# ProPrj_Framethrower_Denise_Rev1.net
KiCad netlist of a schematic drawn in EasyEDA Pro
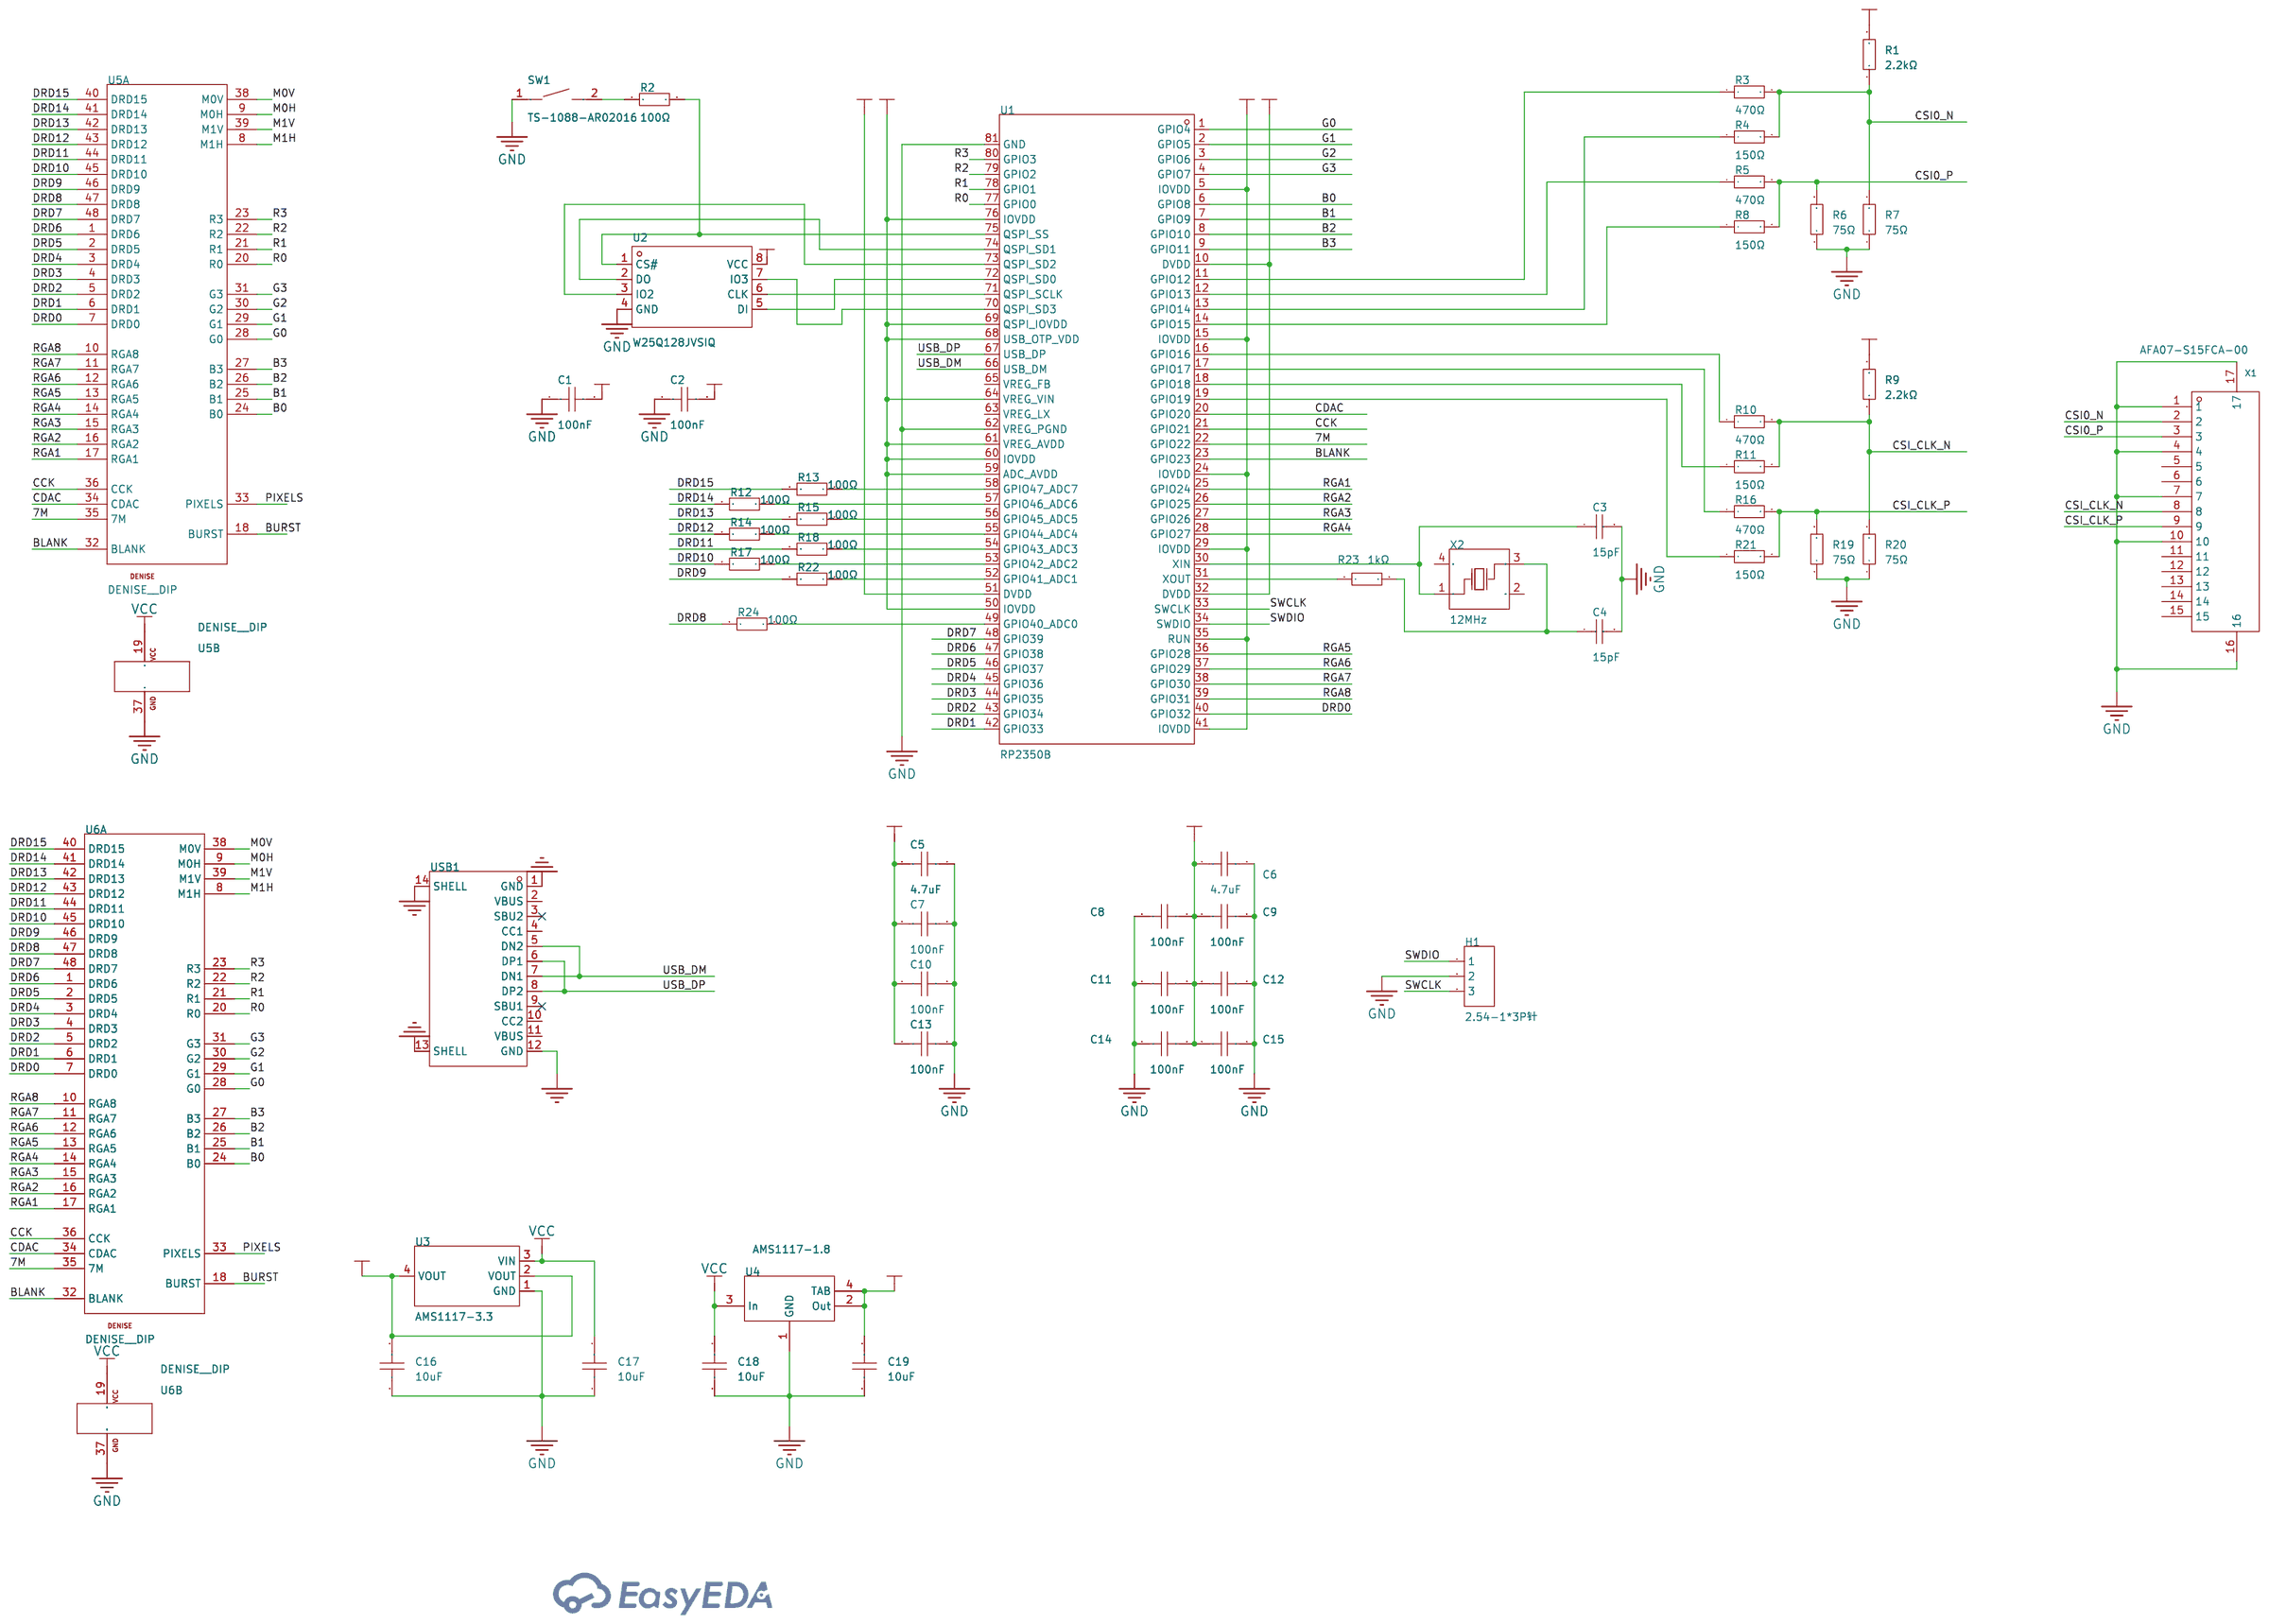
[diagram p0: schematic sheet]

(export (version "E")
  (design (tool "Eeschema 10.0.6"))
  (components
    (comp (ref "C1")
      (value "100nF")
      (footprint "easyedapro:C0603")
      (description "Capacitance:100nF Tolerance:±10% Tolerance:±10% Voltage Rating:50V Temperature Coefficient:X7R")
      (fields
        (field (name "Manufacturer Part") "CC0603KRX7R9BB104")
        (field (name "Manufacturer") "YAGEO(国巨)")
      )
      (libsource (lib "easyedapro") (part "CC0603KRX7R9BB104"))
    )
    (comp (ref "C2")
      (value "100nF")
      (footprint "easyedapro:C0603")
      (description "Capacitance:100nF Tolerance:±10% Tolerance:±10% Voltage Rating:50V Temperature Coefficient:X7R")
      (fields
        (field (name "Manufacturer Part") "CC0603KRX7R9BB104")
        (field (name "Manufacturer") "YAGEO(国巨)")
      )
      (libsource (lib "easyedapro") (part "CC0603KRX7R9BB104"))
    )
    (comp (ref "C3")
      (value "15pF")
      (footprint "easyedapro:C0603")
      (fields
        (field (name "Manufacturer Part") "CL10C150JB8NNNC")
        (field (name "Manufacturer") "SAMSUNG(三星)")
      )
      (libsource (lib "easyedapro") (part "CL10C150JB8NNNC"))
    )
    (comp (ref "C4")
      (value "15pF")
      (footprint "easyedapro:C0603")
      (fields
        (field (name "Manufacturer Part") "CL10C150JB8NNNC")
        (field (name "Manufacturer") "SAMSUNG(三星)")
      )
      (libsource (lib "easyedapro") (part "CL10C150JB8NNNC"))
    )
    (comp (ref "C5")
      (value "4.7uF")
      (footprint "easyedapro:C0603")
      (fields
        (field (name "Manufacturer Part") "CL10A475KO8NNNC")
        (field (name "Manufacturer") "SAMSUNG(三星)")
      )
      (libsource (lib "easyedapro") (part "CL10A475KO8NNNC"))
    )
    (comp (ref "C6")
      (value "4.7uF")
      (footprint "easyedapro:C0603")
      (fields
        (field (name "Manufacturer Part") "CL10A475KO8NNNC")
        (field (name "Manufacturer") "SAMSUNG(三星)")
      )
      (libsource (lib "easyedapro") (part "CL10A475KO8NNNC"))
    )
    (comp (ref "C7")
      (value "100nF")
      (footprint "easyedapro:C0603")
      (description "Capacitance:100nF Tolerance:±10% Tolerance:±10% Voltage Rating:50V Temperature Coefficient:X7R")
      (fields
        (field (name "Manufacturer Part") "CC0603KRX7R9BB104")
        (field (name "Manufacturer") "YAGEO(国巨)")
      )
      (libsource (lib "easyedapro") (part "CC0603KRX7R9BB104"))
    )
    (comp (ref "C8")
      (value "100nF")
      (footprint "easyedapro:C0603")
      (description "Capacitance:100nF Tolerance:±10% Tolerance:±10% Voltage Rating:50V Temperature Coefficient:X7R")
      (fields
        (field (name "Manufacturer Part") "CC0603KRX7R9BB104")
        (field (name "Manufacturer") "YAGEO(国巨)")
      )
      (libsource (lib "easyedapro") (part "CC0603KRX7R9BB104"))
    )
    (comp (ref "C9")
      (value "100nF")
      (footprint "easyedapro:C0603")
      (description "Capacitance:100nF Tolerance:±10% Tolerance:±10% Voltage Rating:50V Temperature Coefficient:X7R")
      (fields
        (field (name "Manufacturer Part") "CC0603KRX7R9BB104")
        (field (name "Manufacturer") "YAGEO(国巨)")
      )
      (libsource (lib "easyedapro") (part "CC0603KRX7R9BB104"))
    )
    (comp (ref "C10")
      (value "100nF")
      (footprint "easyedapro:C0603")
      (description "Capacitance:100nF Tolerance:±10% Tolerance:±10% Voltage Rating:50V Temperature Coefficient:X7R")
      (fields
        (field (name "Manufacturer Part") "CC0603KRX7R9BB104")
        (field (name "Manufacturer") "YAGEO(国巨)")
      )
      (libsource (lib "easyedapro") (part "CC0603KRX7R9BB104"))
    )
    (comp (ref "C11")
      (value "100nF")
      (footprint "easyedapro:C0603")
      (description "Capacitance:100nF Tolerance:±10% Tolerance:±10% Voltage Rating:50V Temperature Coefficient:X7R")
      (fields
        (field (name "Manufacturer Part") "CC0603KRX7R9BB104")
        (field (name "Manufacturer") "YAGEO(国巨)")
      )
      (libsource (lib "easyedapro") (part "CC0603KRX7R9BB104"))
    )
    (comp (ref "C12")
      (value "100nF")
      (footprint "easyedapro:C0603")
      (description "Capacitance:100nF Tolerance:±10% Tolerance:±10% Voltage Rating:50V Temperature Coefficient:X7R")
      (fields
        (field (name "Manufacturer Part") "CC0603KRX7R9BB104")
        (field (name "Manufacturer") "YAGEO(国巨)")
      )
      (libsource (lib "easyedapro") (part "CC0603KRX7R9BB104"))
    )
    (comp (ref "C13")
      (value "100nF")
      (footprint "easyedapro:C0603")
      (description "Capacitance:100nF Tolerance:±10% Tolerance:±10% Voltage Rating:50V Temperature Coefficient:X7R")
      (fields
        (field (name "Manufacturer Part") "CC0603KRX7R9BB104")
        (field (name "Manufacturer") "YAGEO(国巨)")
      )
      (libsource (lib "easyedapro") (part "CC0603KRX7R9BB104"))
    )
    (comp (ref "C14")
      (value "100nF")
      (footprint "easyedapro:C0603")
      (description "Capacitance:100nF Tolerance:±10% Tolerance:±10% Voltage Rating:50V Temperature Coefficient:X7R")
      (fields
        (field (name "Manufacturer Part") "CC0603KRX7R9BB104")
        (field (name "Manufacturer") "YAGEO(国巨)")
      )
      (libsource (lib "easyedapro") (part "CC0603KRX7R9BB104"))
    )
    (comp (ref "C15")
      (value "100nF")
      (footprint "easyedapro:C0603")
      (description "Capacitance:100nF Tolerance:±10% Tolerance:±10% Voltage Rating:50V Temperature Coefficient:X7R")
      (fields
        (field (name "Manufacturer Part") "CC0603KRX7R9BB104")
        (field (name "Manufacturer") "YAGEO(国巨)")
      )
      (libsource (lib "easyedapro") (part "CC0603KRX7R9BB104"))
    )
    (comp (ref "C16")
      (value "10uF")
      (footprint "easyedapro:C0603")
      (fields
        (field (name "Manufacturer Part") "CL10A106KP8NNNC")
        (field (name "Manufacturer") "SAMSUNG(三星)")
      )
      (libsource (lib "easyedapro") (part "CL10A106KP8NNNC"))
    )
    (comp (ref "C17")
      (value "10uF")
      (footprint "easyedapro:C0603")
      (fields
        (field (name "Manufacturer Part") "CL10A106KP8NNNC")
        (field (name "Manufacturer") "SAMSUNG(三星)")
      )
      (libsource (lib "easyedapro") (part "CL10A106KP8NNNC"))
    )
    (comp (ref "C18")
      (value "10uF")
      (footprint "easyedapro:C0603")
      (fields
        (field (name "Manufacturer Part") "CL10A106KP8NNNC")
        (field (name "Manufacturer") "SAMSUNG(三星)")
      )
      (libsource (lib "easyedapro") (part "CL10A106KP8NNNC"))
    )
    (comp (ref "C19")
      (value "10uF")
      (footprint "easyedapro:C0603")
      (fields
        (field (name "Manufacturer Part") "CL10A106KP8NNNC")
        (field (name "Manufacturer") "SAMSUNG(三星)")
      )
      (libsource (lib "easyedapro") (part "CL10A106KP8NNNC"))
    )
    (comp (ref "H1")
      (value "2.54-1*3P针")
      (footprint "easyedapro:HDR-TH_3P-P2.54-V-M-1")
      (fields (field (name "Manufacturer") "BOOMELE(博穆精密)"))
      (libsource (lib "easyedapro") (part "Header-Male-2.54_1x3"))
    )
    (comp (ref "R1")
      (value "2.2kΩ")
      (footprint "easyedapro:R0603")
      (fields
        (field (name "Manufacturer Part") "0603WAF2201T5E")
        (field (name "Manufacturer") "UNI-ROYAL(厚声)")
      )
      (libsource (lib "easyedapro") (part "0603WAF5600T5E"))
    )
    (comp (ref "R2")
      (value "100Ω")
      (footprint "easyedapro:R0603")
      (fields
        (field (name "Manufacturer Part") "0603WAF1000T5E")
        (field (name "Manufacturer") "UNI-ROYAL(厚声)")
      )
      (libsource (lib "easyedapro") (part "0603WAF1000T5E"))
    )
    (comp (ref "R3")
      (value "470Ω")
      (footprint "easyedapro:R0603")
      (fields
        (field (name "Manufacturer Part") "0603WAF4700T5E")
        (field (name "Manufacturer") "UNI-ROYAL(厚声)")
      )
      (libsource (lib "easyedapro") (part "0603WAF2400T5E"))
    )
    (comp (ref "R4")
      (value "150Ω")
      (footprint "easyedapro:R0603")
      (fields
        (field (name "Manufacturer Part") "0603WAF1500T5E")
        (field (name "Manufacturer") "UNI-ROYAL(厚声)")
      )
      (libsource (lib "easyedapro") (part "0603WAF750JT5E"))
    )
    (comp (ref "R5")
      (value "470Ω")
      (footprint "easyedapro:R0603")
      (fields
        (field (name "Manufacturer Part") "0603WAF4700T5E")
        (field (name "Manufacturer") "UNI-ROYAL(厚声)")
      )
      (libsource (lib "easyedapro") (part "0603WAF2400T5E"))
    )
    (comp (ref "R6")
      (value "75Ω")
      (footprint "easyedapro:R0603")
      (fields
        (field (name "Manufacturer Part") "0603WAF750JT5E")
        (field (name "Manufacturer") "UNI-ROYAL(厚声)")
      )
      (libsource (lib "easyedapro") (part "0603WAF270JT5E"))
    )
    (comp (ref "R7")
      (value "75Ω")
      (footprint "easyedapro:R0603")
      (fields
        (field (name "Manufacturer Part") "0603WAF750JT5E")
        (field (name "Manufacturer") "UNI-ROYAL(厚声)")
      )
      (libsource (lib "easyedapro") (part "0603WAF270JT5E"))
    )
    (comp (ref "R8")
      (value "150Ω")
      (footprint "easyedapro:R0603")
      (fields
        (field (name "Manufacturer Part") "0603WAF1500T5E")
        (field (name "Manufacturer") "UNI-ROYAL(厚声)")
      )
      (libsource (lib "easyedapro") (part "0603WAF750JT5E"))
    )
    (comp (ref "R9")
      (value "2.2kΩ")
      (footprint "easyedapro:R0603")
      (fields
        (field (name "Manufacturer Part") "0603WAF2201T5E")
        (field (name "Manufacturer") "UNI-ROYAL(厚声)")
      )
      (libsource (lib "easyedapro") (part "0603WAF5600T5E"))
    )
    (comp (ref "R10")
      (value "470Ω")
      (footprint "easyedapro:R0603")
      (fields
        (field (name "Manufacturer Part") "0603WAF4700T5E")
        (field (name "Manufacturer") "UNI-ROYAL(厚声)")
      )
      (libsource (lib "easyedapro") (part "0603WAF2400T5E"))
    )
    (comp (ref "R11")
      (value "150Ω")
      (footprint "easyedapro:R0603")
      (fields
        (field (name "Manufacturer Part") "0603WAF1500T5E")
        (field (name "Manufacturer") "UNI-ROYAL(厚声)")
      )
      (libsource (lib "easyedapro") (part "0603WAF750JT5E"))
    )
    (comp (ref "R12")
      (value "100Ω")
      (footprint "easyedapro:R0603")
      (fields
        (field (name "Manufacturer Part") "0603WAF1000T5E")
        (field (name "Manufacturer") "UNI-ROYAL(厚声)")
      )
      (libsource (lib "easyedapro") (part "0603WAF1000T5E"))
    )
    (comp (ref "R13")
      (value "100Ω")
      (footprint "easyedapro:R0603")
      (fields
        (field (name "Manufacturer Part") "0603WAF1000T5E")
        (field (name "Manufacturer") "UNI-ROYAL(厚声)")
      )
      (libsource (lib "easyedapro") (part "0603WAF1000T5E"))
    )
    (comp (ref "R14")
      (value "100Ω")
      (footprint "easyedapro:R0603")
      (fields
        (field (name "Manufacturer Part") "0603WAF1000T5E")
        (field (name "Manufacturer") "UNI-ROYAL(厚声)")
      )
      (libsource (lib "easyedapro") (part "0603WAF1000T5E"))
    )
    (comp (ref "R15")
      (value "100Ω")
      (footprint "easyedapro:R0603")
      (fields
        (field (name "Manufacturer Part") "0603WAF1000T5E")
        (field (name "Manufacturer") "UNI-ROYAL(厚声)")
      )
      (libsource (lib "easyedapro") (part "0603WAF1000T5E"))
    )
    (comp (ref "R16")
      (value "470Ω")
      (footprint "easyedapro:R0603")
      (fields
        (field (name "Manufacturer Part") "0603WAF4700T5E")
        (field (name "Manufacturer") "UNI-ROYAL(厚声)")
      )
      (libsource (lib "easyedapro") (part "0603WAF2400T5E"))
    )
    (comp (ref "R17")
      (value "100Ω")
      (footprint "easyedapro:R0603")
      (fields
        (field (name "Manufacturer Part") "0603WAF1000T5E")
        (field (name "Manufacturer") "UNI-ROYAL(厚声)")
      )
      (libsource (lib "easyedapro") (part "0603WAF1000T5E"))
    )
    (comp (ref "R18")
      (value "100Ω")
      (footprint "easyedapro:R0603")
      (fields
        (field (name "Manufacturer Part") "0603WAF1000T5E")
        (field (name "Manufacturer") "UNI-ROYAL(厚声)")
      )
      (libsource (lib "easyedapro") (part "0603WAF1000T5E"))
    )
    (comp (ref "R19")
      (value "75Ω")
      (footprint "easyedapro:R0603")
      (fields
        (field (name "Manufacturer Part") "0603WAF750JT5E")
        (field (name "Manufacturer") "UNI-ROYAL(厚声)")
      )
      (libsource (lib "easyedapro") (part "0603WAF270JT5E"))
    )
    (comp (ref "R20")
      (value "75Ω")
      (footprint "easyedapro:R0603")
      (fields
        (field (name "Manufacturer Part") "0603WAF750JT5E")
        (field (name "Manufacturer") "UNI-ROYAL(厚声)")
      )
      (libsource (lib "easyedapro") (part "0603WAF270JT5E"))
    )
    (comp (ref "R21")
      (value "150Ω")
      (footprint "easyedapro:R0603")
      (fields
        (field (name "Manufacturer Part") "0603WAF1500T5E")
        (field (name "Manufacturer") "UNI-ROYAL(厚声)")
      )
      (libsource (lib "easyedapro") (part "0603WAF750JT5E"))
    )
    (comp (ref "R22")
      (value "100Ω")
      (footprint "easyedapro:R0603")
      (fields
        (field (name "Manufacturer Part") "0603WAF1000T5E")
        (field (name "Manufacturer") "UNI-ROYAL(厚声)")
      )
      (libsource (lib "easyedapro") (part "0603WAF1000T5E"))
    )
    (comp (ref "R23")
      (value "1kΩ")
      (footprint "easyedapro:R0603")
      (fields
        (field (name "Manufacturer Part") "0603WAF1001T5E")
        (field (name "Manufacturer") "UNI-ROYAL(厚声)")
      )
      (libsource (lib "easyedapro") (part "0603WAF1001T5E"))
    )
    (comp (ref "R24")
      (value "100Ω")
      (footprint "easyedapro:R0603")
      (fields
        (field (name "Manufacturer Part") "0603WAF1000T5E")
        (field (name "Manufacturer") "UNI-ROYAL(厚声)")
      )
      (libsource (lib "easyedapro") (part "0603WAF1000T5E"))
    )
    (comp (ref "SW1")
      (value "TS-1088-AR02016")
      (footprint "easyedapro:SW-SMD_L3.9-W3.0-P4.45")
      (fields (field (name "Manufacturer") "XUNPU(讯普)"))
      (libsource (lib "easyedapro") (part "TS-1088-AR02016"))
    )
    (comp (ref "U1")
      (value "RP2350B")
      (footprint "easyedapro:QFN-80_L10.0-W10.0-P0.40-TL-EP3.4")
      (fields (field (name "Manufacturer") "Raspberry Pi(树莓派)"))
      (libsource (lib "easyedapro") (part "RP2350B_C42415655"))
    )
    (comp (ref "U2")
      (value "W25Q128JVSIQ")
      (footprint "easyedapro:SOIC-8_L5.3-W5.3-P1.27-LS8.0-BL")
      (fields (field (name "Manufacturer") "WINBOND(华邦)"))
      (libsource (lib "easyedapro") (part "W25Q128JVSIQTR"))
    )
    (comp (ref "U3")
      (value "AMS1117-3.3")
      (footprint "easyedapro:SOT-223-3_L6.5-W3.4-P2.30-LS7.0-BR")
      (fields (field (name "Manufacturer") "AMS"))
      (libsource (lib "easyedapro") (part "AMS1117-3.3"))
    )
    (comp (ref "U4")
      (value "AMS1117-1.8")
      (footprint "easyedapro:SOT-223-4_L6.5-W3.5-P2.30-LS7.0-BR")
      (fields (field (name "Manufacturer") "AMS"))
      (libsource (lib "easyedapro") (part "AMS1117-1.8"))
    )
    (comp (ref "U5")
      (value "DENISE__DIP")
      (footprint "easyedapro:DIP48-6")
      (libsource (lib "easyedapro") (part "DENISE__DIP"))
    )
    (comp (ref "U6")
      (value "DENISE__DIP")
      (footprint "easyedapro:DIP48-6")
      (libsource (lib "easyedapro") (part "DENISE__DIP"))
    )
    (comp (ref "USB1")
      (value "TYPE-C 16PIN 2MD(073)")
      (footprint "easyedapro:USB-C-SMD_TYPE-C-6PIN-2MD-073")
      (description "连接器类型:Type-C;标准:-;公母:母;端口数量:1;触点数量:16P;安装方式:卧贴;额定电流 - 电源:5A;工作温度范围:-25°C~+85°C;")
      (fields (field (name "Manufacturer") "SHOU HAN(首韩)"))
      (libsource (lib "easyedapro") (part "TYPE-C 16PIN 2MD(073)"))
    )
    (comp (ref "X1")
      (value "AFA07-S15FCA-00")
      (footprint "easyedapro:FPC-SMD_15P-P1.00_JS_AFA07-S15XXX")
      (fields (field (name "Manufacturer") "JS(钜硕电子)"))
      (libsource (lib "easyedapro") (part "AFA07-S15FCA-00"))
    )
    (comp (ref "X2")
      (value "12MHz")
      (footprint "easyedapro:CRYSTAL-SMD_4P-L3.2-W2.5-BL")
      (fields (field (name "Manufacturer Part") "X322512MSB4SI") (field (name "Manufacturer") "YXC(扬兴晶振)"))
      (libsource (lib "easyedapro") (part "X322512MSB4SI"))
    )
  )
  (nets
    (net (code "1") (name "/7M") (class "Default")
      (node (ref "U1") (pin "22") (pinfunction "GPIO22_22") (pintype "unspecified"))
      (node (ref "U5") (pin "35") (pinfunction "7M_35") (pintype "input"))
      (node (ref "U6") (pin "35") (pinfunction "7M_35") (pintype "input"))
    )
    (net (code "2") (name "/B0") (class "Default")
      (node (ref "U1") (pin "6") (pinfunction "GPIO8_6") (pintype "unspecified"))
      (node (ref "U5") (pin "24") (pinfunction "B0_24") (pintype "output"))
      (node (ref "U6") (pin "24") (pinfunction "B0_24") (pintype "output"))
    )
    (net (code "3") (name "/B1") (class "Default")
      (node (ref "U1") (pin "7") (pinfunction "GPIO9_7") (pintype "unspecified"))
      (node (ref "U5") (pin "25") (pinfunction "B1_25") (pintype "output"))
      (node (ref "U6") (pin "25") (pinfunction "B1_25") (pintype "output"))
    )
    (net (code "4") (name "/B2") (class "Default")
      (node (ref "U1") (pin "8") (pinfunction "GPIO10_8") (pintype "unspecified"))
      (node (ref "U5") (pin "26") (pinfunction "B2_26") (pintype "output"))
      (node (ref "U6") (pin "26") (pinfunction "B2_26") (pintype "output"))
    )
    (net (code "5") (name "/B3") (class "Default")
      (node (ref "U1") (pin "9") (pinfunction "GPIO11_9") (pintype "unspecified"))
      (node (ref "U5") (pin "27") (pinfunction "B3_27") (pintype "output"))
      (node (ref "U6") (pin "27") (pinfunction "B3_27") (pintype "output"))
    )
    (net (code "6") (name "/BLANK") (class "Default")
      (node (ref "U1") (pin "23") (pinfunction "GPIO23_23") (pintype "unspecified"))
      (node (ref "U5") (pin "32") (pinfunction "BLANK_32") (pintype "input"))
      (node (ref "U6") (pin "32") (pinfunction "BLANK_32") (pintype "input"))
    )
    (net (code "7") (name "/BURST") (class "Default")
      (node (ref "U5") (pin "18") (pinfunction "BURST_18") (pintype "output"))
      (node (ref "U6") (pin "18") (pinfunction "BURST_18") (pintype "output"))
    )
    (net (code "8") (name "/CCK") (class "Default")
      (node (ref "U1") (pin "21") (pinfunction "GPIO21_21") (pintype "unspecified"))
      (node (ref "U5") (pin "36") (pinfunction "CCK_36") (pintype "input"))
      (node (ref "U6") (pin "36") (pinfunction "CCK_36") (pintype "input"))
    )
    (net (code "9") (name "/CDAC") (class "Default")
      (node (ref "U1") (pin "20") (pinfunction "GPIO20_20") (pintype "unspecified"))
      (node (ref "U5") (pin "34") (pinfunction "CDAC_34") (pintype "input"))
      (node (ref "U6") (pin "34") (pinfunction "CDAC_34") (pintype "input"))
    )
    (net (code "10") (name "/CSI0_N") (class "Default")
      (node (ref "R1") (pin "1") (pinfunction "1_1") (pintype "input"))
      (node (ref "R3") (pin "2") (pinfunction "2_2") (pintype "input"))
      (node (ref "R4") (pin "2") (pinfunction "2_2") (pintype "input"))
      (node (ref "R7") (pin "2") (pinfunction "2_2") (pintype "input"))
      (node (ref "X1") (pin "2") (pinfunction "2_2") (pintype "input"))
    )
    (net (code "11") (name "/CSI0_P") (class "Default")
      (node (ref "R5") (pin "2") (pinfunction "2_2") (pintype "input"))
      (node (ref "R6") (pin "2") (pinfunction "2_2") (pintype "input"))
      (node (ref "R8") (pin "2") (pinfunction "2_2") (pintype "input"))
      (node (ref "X1") (pin "3") (pinfunction "3_3") (pintype "input"))
    )
    (net (code "12") (name "/CSI_CLK_N") (class "Default")
      (node (ref "R10") (pin "2") (pinfunction "2_2") (pintype "input"))
      (node (ref "R11") (pin "2") (pinfunction "2_2") (pintype "input"))
      (node (ref "R20") (pin "2") (pinfunction "2_2") (pintype "input"))
      (node (ref "R9") (pin "1") (pinfunction "1_1") (pintype "input"))
      (node (ref "X1") (pin "8") (pinfunction "8_8") (pintype "input"))
    )
    (net (code "13") (name "/CSI_CLK_P") (class "Default")
      (node (ref "R16") (pin "2") (pinfunction "2_2") (pintype "input"))
      (node (ref "R19") (pin "2") (pinfunction "2_2") (pintype "input"))
      (node (ref "R21") (pin "2") (pinfunction "2_2") (pintype "input"))
      (node (ref "X1") (pin "9") (pinfunction "9_9") (pintype "input"))
    )
    (net (code "14") (name "/DRD0") (class "Default")
      (node (ref "U1") (pin "40") (pinfunction "GPIO32_40") (pintype "unspecified"))
      (node (ref "U5") (pin "7") (pinfunction "DRD0_7") (pintype "bidirectional"))
      (node (ref "U6") (pin "7") (pinfunction "DRD0_7") (pintype "bidirectional"))
    )
    (net (code "15") (name "/DRD1") (class "Default")
      (node (ref "U1") (pin "42") (pinfunction "GPIO33_42") (pintype "unspecified"))
      (node (ref "U5") (pin "6") (pinfunction "DRD1_6") (pintype "bidirectional"))
      (node (ref "U6") (pin "6") (pinfunction "DRD1_6") (pintype "bidirectional"))
    )
    (net (code "16") (name "/DRD2") (class "Default")
      (node (ref "U1") (pin "43") (pinfunction "GPIO34_43") (pintype "unspecified"))
      (node (ref "U5") (pin "5") (pinfunction "DRD2_5") (pintype "bidirectional"))
      (node (ref "U6") (pin "5") (pinfunction "DRD2_5") (pintype "bidirectional"))
    )
    (net (code "17") (name "/DRD3") (class "Default")
      (node (ref "U1") (pin "44") (pinfunction "GPIO35_44") (pintype "unspecified"))
      (node (ref "U5") (pin "4") (pinfunction "DRD3_4") (pintype "bidirectional"))
      (node (ref "U6") (pin "4") (pinfunction "DRD3_4") (pintype "bidirectional"))
    )
    (net (code "18") (name "/DRD4") (class "Default")
      (node (ref "U1") (pin "45") (pinfunction "GPIO36_45") (pintype "unspecified"))
      (node (ref "U5") (pin "3") (pinfunction "DRD4_3") (pintype "bidirectional"))
      (node (ref "U6") (pin "3") (pinfunction "DRD4_3") (pintype "bidirectional"))
    )
    (net (code "19") (name "/DRD5") (class "Default")
      (node (ref "U1") (pin "46") (pinfunction "GPIO37_46") (pintype "unspecified"))
      (node (ref "U5") (pin "2") (pinfunction "DRD5_2") (pintype "bidirectional"))
      (node (ref "U6") (pin "2") (pinfunction "DRD5_2") (pintype "bidirectional"))
    )
    (net (code "20") (name "/DRD6") (class "Default")
      (node (ref "U1") (pin "47") (pinfunction "GPIO38_47") (pintype "unspecified"))
      (node (ref "U5") (pin "1") (pinfunction "DRD6_1") (pintype "bidirectional"))
      (node (ref "U6") (pin "1") (pinfunction "DRD6_1") (pintype "bidirectional"))
    )
    (net (code "21") (name "/DRD7") (class "Default")
      (node (ref "U1") (pin "48") (pinfunction "GPIO39_48") (pintype "unspecified"))
      (node (ref "U5") (pin "48") (pinfunction "DRD7_48") (pintype "bidirectional"))
      (node (ref "U6") (pin "48") (pinfunction "DRD7_48") (pintype "bidirectional"))
    )
    (net (code "22") (name "/DRD8") (class "Default")
      (node (ref "R24") (pin "2") (pinfunction "2_2") (pintype "input"))
      (node (ref "U5") (pin "47") (pinfunction "DRD8_47") (pintype "bidirectional"))
      (node (ref "U6") (pin "47") (pinfunction "DRD8_47") (pintype "bidirectional"))
    )
    (net (code "23") (name "/DRD9") (class "Default")
      (node (ref "R22") (pin "2") (pinfunction "2_2") (pintype "input"))
      (node (ref "U5") (pin "46") (pinfunction "DRD9_46") (pintype "bidirectional"))
      (node (ref "U6") (pin "46") (pinfunction "DRD9_46") (pintype "bidirectional"))
    )
    (net (code "24") (name "/DRD10") (class "Default")
      (node (ref "R17") (pin "2") (pinfunction "2_2") (pintype "input"))
      (node (ref "U5") (pin "45") (pinfunction "DRD10_45") (pintype "bidirectional"))
      (node (ref "U6") (pin "45") (pinfunction "DRD10_45") (pintype "bidirectional"))
    )
    (net (code "25") (name "/DRD11") (class "Default")
      (node (ref "R18") (pin "2") (pinfunction "2_2") (pintype "input"))
      (node (ref "U5") (pin "44") (pinfunction "DRD11_44") (pintype "bidirectional"))
      (node (ref "U6") (pin "44") (pinfunction "DRD11_44") (pintype "bidirectional"))
    )
    (net (code "26") (name "/DRD12") (class "Default")
      (node (ref "R14") (pin "2") (pinfunction "2_2") (pintype "input"))
      (node (ref "U5") (pin "43") (pinfunction "DRD12_43") (pintype "bidirectional"))
      (node (ref "U6") (pin "43") (pinfunction "DRD12_43") (pintype "bidirectional"))
    )
    (net (code "27") (name "/DRD13") (class "Default")
      (node (ref "R15") (pin "2") (pinfunction "2_2") (pintype "input"))
      (node (ref "U5") (pin "42") (pinfunction "DRD13_42") (pintype "bidirectional"))
      (node (ref "U6") (pin "42") (pinfunction "DRD13_42") (pintype "bidirectional"))
    )
    (net (code "28") (name "/DRD14") (class "Default")
      (node (ref "R12") (pin "2") (pinfunction "2_2") (pintype "input"))
      (node (ref "U5") (pin "41") (pinfunction "DRD14_41") (pintype "bidirectional"))
      (node (ref "U6") (pin "41") (pinfunction "DRD14_41") (pintype "bidirectional"))
    )
    (net (code "29") (name "/DRD15") (class "Default")
      (node (ref "R13") (pin "2") (pinfunction "2_2") (pintype "input"))
      (node (ref "U5") (pin "40") (pinfunction "DRD15_40") (pintype "bidirectional"))
      (node (ref "U6") (pin "40") (pinfunction "DRD15_40") (pintype "bidirectional"))
    )
    (net (code "30") (name "/G0") (class "Default")
      (node (ref "U1") (pin "1") (pinfunction "GPIO4_1") (pintype "unspecified"))
      (node (ref "U5") (pin "28") (pinfunction "G0_28") (pintype "output"))
      (node (ref "U6") (pin "28") (pinfunction "G0_28") (pintype "output"))
    )
    (net (code "31") (name "/G1") (class "Default")
      (node (ref "U1") (pin "2") (pinfunction "GPIO5_2") (pintype "unspecified"))
      (node (ref "U5") (pin "29") (pinfunction "G1_29") (pintype "output"))
      (node (ref "U6") (pin "29") (pinfunction "G1_29") (pintype "output"))
    )
    (net (code "32") (name "/G2") (class "Default")
      (node (ref "U1") (pin "3") (pinfunction "GPIO6_3") (pintype "unspecified"))
      (node (ref "U5") (pin "30") (pinfunction "G2_30") (pintype "output"))
      (node (ref "U6") (pin "30") (pinfunction "G2_30") (pintype "output"))
    )
    (net (code "33") (name "/G3") (class "Default")
      (node (ref "U1") (pin "4") (pinfunction "GPIO7_4") (pintype "unspecified"))
      (node (ref "U5") (pin "31") (pinfunction "G3_31") (pintype "output"))
      (node (ref "U6") (pin "31") (pinfunction "G3_31") (pintype "output"))
    )
    (net (code "34") (name "/M0H") (class "Default")
      (node (ref "U5") (pin "9") (pinfunction "M0H_9") (pintype "input"))
      (node (ref "U6") (pin "9") (pinfunction "M0H_9") (pintype "input"))
    )
    (net (code "35") (name "/M0V") (class "Default")
      (node (ref "U5") (pin "38") (pinfunction "M0V_38") (pintype "input"))
      (node (ref "U6") (pin "38") (pinfunction "M0V_38") (pintype "input"))
    )
    (net (code "36") (name "/M1H") (class "Default")
      (node (ref "U5") (pin "8") (pinfunction "M1H_8") (pintype "input"))
      (node (ref "U6") (pin "8") (pinfunction "M1H_8") (pintype "input"))
    )
    (net (code "37") (name "/M1V") (class "Default")
      (node (ref "U5") (pin "39") (pinfunction "M1V_39") (pintype "input"))
      (node (ref "U6") (pin "39") (pinfunction "M1V_39") (pintype "input"))
    )
    (net (code "38") (name "/PIXELS") (class "Default")
      (node (ref "U5") (pin "33") (pinfunction "PIXELS_33") (pintype "output"))
      (node (ref "U6") (pin "33") (pinfunction "PIXELS_33") (pintype "output"))
    )
    (net (code "39") (name "/R0") (class "Default")
      (node (ref "U1") (pin "77") (pinfunction "GPIO0_77") (pintype "unspecified"))
      (node (ref "U5") (pin "20") (pinfunction "R0_20") (pintype "output"))
      (node (ref "U6") (pin "20") (pinfunction "R0_20") (pintype "output"))
    )
    (net (code "40") (name "/R1") (class "Default")
      (node (ref "U1") (pin "78") (pinfunction "GPIO1_78") (pintype "unspecified"))
      (node (ref "U5") (pin "21") (pinfunction "R1_21") (pintype "output"))
      (node (ref "U6") (pin "21") (pinfunction "R1_21") (pintype "output"))
    )
    (net (code "41") (name "/R2") (class "Default")
      (node (ref "U1") (pin "79") (pinfunction "GPIO2_79") (pintype "unspecified"))
      (node (ref "U5") (pin "22") (pinfunction "R2_22") (pintype "output"))
      (node (ref "U6") (pin "22") (pinfunction "R2_22") (pintype "output"))
    )
    (net (code "42") (name "/R3") (class "Default")
      (node (ref "U1") (pin "80") (pinfunction "GPIO3_80") (pintype "unspecified"))
      (node (ref "U5") (pin "23") (pinfunction "R3_23") (pintype "output"))
      (node (ref "U6") (pin "23") (pinfunction "R3_23") (pintype "output"))
    )
    (net (code "43") (name "/RGA1") (class "Default")
      (node (ref "U1") (pin "25") (pinfunction "GPIO24_25") (pintype "unspecified"))
      (node (ref "U5") (pin "17") (pinfunction "RGA1_17") (pintype "input"))
      (node (ref "U6") (pin "17") (pinfunction "RGA1_17") (pintype "input"))
    )
    (net (code "44") (name "/RGA2") (class "Default")
      (node (ref "U1") (pin "26") (pinfunction "GPIO25_26") (pintype "unspecified"))
      (node (ref "U5") (pin "16") (pinfunction "RGA2_16") (pintype "input"))
      (node (ref "U6") (pin "16") (pinfunction "RGA2_16") (pintype "input"))
    )
    (net (code "45") (name "/RGA3") (class "Default")
      (node (ref "U1") (pin "27") (pinfunction "GPIO26_27") (pintype "unspecified"))
      (node (ref "U5") (pin "15") (pinfunction "RGA3_15") (pintype "input"))
      (node (ref "U6") (pin "15") (pinfunction "RGA3_15") (pintype "input"))
    )
    (net (code "46") (name "/RGA4") (class "Default")
      (node (ref "U1") (pin "28") (pinfunction "GPIO27_28") (pintype "unspecified"))
      (node (ref "U5") (pin "14") (pinfunction "RGA4_14") (pintype "input"))
      (node (ref "U6") (pin "14") (pinfunction "RGA4_14") (pintype "input"))
    )
    (net (code "47") (name "/RGA5") (class "Default")
      (node (ref "U1") (pin "36") (pinfunction "GPIO28_36") (pintype "unspecified"))
      (node (ref "U5") (pin "13") (pinfunction "RGA5_13") (pintype "input"))
      (node (ref "U6") (pin "13") (pinfunction "RGA5_13") (pintype "input"))
    )
    (net (code "48") (name "/RGA6") (class "Default")
      (node (ref "U1") (pin "37") (pinfunction "GPIO29_37") (pintype "unspecified"))
      (node (ref "U5") (pin "12") (pinfunction "RGA6_12") (pintype "input"))
      (node (ref "U6") (pin "12") (pinfunction "RGA6_12") (pintype "input"))
    )
    (net (code "49") (name "/RGA7") (class "Default")
      (node (ref "U1") (pin "38") (pinfunction "GPIO30_38") (pintype "unspecified"))
      (node (ref "U5") (pin "11") (pinfunction "RGA7_11") (pintype "input"))
      (node (ref "U6") (pin "11") (pinfunction "RGA7_11") (pintype "input"))
    )
    (net (code "50") (name "/RGA8") (class "Default")
      (node (ref "U1") (pin "39") (pinfunction "GPIO31_39") (pintype "unspecified"))
      (node (ref "U5") (pin "10") (pinfunction "RGA8_10") (pintype "input"))
      (node (ref "U6") (pin "10") (pinfunction "RGA8_10") (pintype "input"))
    )
    (net (code "51") (name "/SWCLK") (class "Default")
      (node (ref "H1") (pin "3") (pinfunction "3_3") (pintype "input"))
      (node (ref "U1") (pin "33") (pinfunction "SWCLK_33") (pintype "unspecified"))
    )
    (net (code "52") (name "/SWDIO") (class "Default")
      (node (ref "H1") (pin "1") (pinfunction "1_1") (pintype "input"))
      (node (ref "U1") (pin "34") (pinfunction "SWDIO_34") (pintype "unspecified"))
    )
    (net (code "53") (name "/USB_DM") (class "Default")
      (node (ref "U1") (pin "66") (pinfunction "USB_DM_66") (pintype "unspecified"))
      (node (ref "USB1") (pin "5") (pinfunction "DN2_5") (pintype "unspecified"))
      (node (ref "USB1") (pin "7") (pinfunction "DN1_7") (pintype "unspecified"))
    )
    (net (code "54") (name "/USB_DP") (class "Default")
      (node (ref "U1") (pin "67") (pinfunction "USB_DP_67") (pintype "unspecified"))
      (node (ref "USB1") (pin "6") (pinfunction "DP1_6") (pintype "unspecified"))
      (node (ref "USB1") (pin "8") (pinfunction "DP2_8") (pintype "unspecified"))
    )
    (net (code "55") (name "GND") (class "Default")
      (node (ref "C1") (pin "1") (pinfunction "1_1") (pintype "unspecified"))
      (node (ref "C10") (pin "2") (pinfunction "2_2") (pintype "unspecified"))
      (node (ref "C11") (pin "1") (pinfunction "1_1") (pintype "unspecified"))
      (node (ref "C12") (pin "2") (pinfunction "2_2") (pintype "unspecified"))
      (node (ref "C13") (pin "2") (pinfunction "2_2") (pintype "unspecified"))
      (node (ref "C14") (pin "1") (pinfunction "1_1") (pintype "unspecified"))
      (node (ref "C15") (pin "2") (pinfunction "2_2") (pintype "unspecified"))
      (node (ref "C16") (pin "1") (pinfunction "1_1") (pintype "unspecified"))
      (node (ref "C17") (pin "1") (pinfunction "1_1") (pintype "unspecified"))
      (node (ref "C18") (pin "1") (pinfunction "1_1") (pintype "unspecified"))
      (node (ref "C19") (pin "1") (pinfunction "1_1") (pintype "unspecified"))
      (node (ref "C2") (pin "1") (pinfunction "1_1") (pintype "unspecified"))
      (node (ref "C3") (pin "2") (pinfunction "2_2") (pintype "input"))
      (node (ref "C4") (pin "2") (pinfunction "2_2") (pintype "input"))
      (node (ref "C5") (pin "2") (pinfunction "2_2") (pintype "unspecified"))
      (node (ref "C6") (pin "2") (pinfunction "2_2") (pintype "unspecified"))
      (node (ref "C7") (pin "2") (pinfunction "2_2") (pintype "unspecified"))
      (node (ref "C8") (pin "1") (pinfunction "1_1") (pintype "unspecified"))
      (node (ref "C9") (pin "2") (pinfunction "2_2") (pintype "unspecified"))
      (node (ref "H1") (pin "2") (pinfunction "2_2") (pintype "input"))
      (node (ref "R19") (pin "1") (pinfunction "1_1") (pintype "input"))
      (node (ref "R20") (pin "1") (pinfunction "1_1") (pintype "input"))
      (node (ref "R6") (pin "1") (pinfunction "1_1") (pintype "input"))
      (node (ref "R7") (pin "1") (pinfunction "1_1") (pintype "input"))
      (node (ref "SW1") (pin "1") (pinfunction "1_1") (pintype "unspecified"))
      (node (ref "U1") (pin "62") (pinfunction "VREG_PGND_62") (pintype "unspecified"))
      (node (ref "U1") (pin "81") (pinfunction "GND_81") (pintype "unspecified"))
      (node (ref "U2") (pin "4") (pinfunction "GND_4") (pintype "unspecified"))
      (node (ref "U3") (pin "1") (pinfunction "GND_1") (pintype "unspecified"))
      (node (ref "U4") (pin "1") (pinfunction "GND_1") (pintype "unspecified"))
      (node (ref "U5") (pin "37") (pinfunction "GND1_37") (pintype "unspecified"))
      (node (ref "U6") (pin "37") (pinfunction "GND1_37") (pintype "unspecified"))
      (node (ref "USB1") (pin "1") (pinfunction "GND_1") (pintype "unspecified"))
      (node (ref "USB1") (pin "12") (pinfunction "GND_12") (pintype "unspecified"))
      (node (ref "USB1") (pin "13") (pinfunction "SHELL_13") (pintype "unspecified"))
      (node (ref "USB1") (pin "14") (pinfunction "SHELL_14") (pintype "unspecified"))
      (node (ref "X1") (pin "1") (pinfunction "1_1") (pintype "input"))
      (node (ref "X1") (pin "10") (pinfunction "10_10") (pintype "input"))
      (node (ref "X1") (pin "16") (pinfunction "16_16") (pintype "input"))
      (node (ref "X1") (pin "17") (pinfunction "17_17") (pintype "input"))
      (node (ref "X1") (pin "4") (pinfunction "4_4") (pintype "input"))
      (node (ref "X1") (pin "7") (pinfunction "7_7") (pintype "input"))
    )
    (net (code "56") (name "Net-(R2-Pad2)") (class "Default")
      (node (ref "R2") (pin "2") (pinfunction "2_2") (pintype "input"))
      (node (ref "SW1") (pin "2") (pinfunction "2_2") (pintype "unspecified"))
    )
    (net (code "57") (name "Net-(U1-GPIO12)") (class "Default")
      (node (ref "R3") (pin "1") (pinfunction "1_1") (pintype "input"))
      (node (ref "U1") (pin "11") (pinfunction "GPIO12_11") (pintype "unspecified"))
    )
    (net (code "58") (name "Net-(U1-GPIO13)") (class "Default")
      (node (ref "R5") (pin "1") (pinfunction "1_1") (pintype "input"))
      (node (ref "U1") (pin "12") (pinfunction "GPIO13_12") (pintype "unspecified"))
    )
    (net (code "59") (name "Net-(U1-GPIO14)") (class "Default")
      (node (ref "R4") (pin "1") (pinfunction "1_1") (pintype "input"))
      (node (ref "U1") (pin "13") (pinfunction "GPIO14_13") (pintype "unspecified"))
    )
    (net (code "60") (name "Net-(U1-GPIO15)") (class "Default")
      (node (ref "R8") (pin "1") (pinfunction "1_1") (pintype "input"))
      (node (ref "U1") (pin "14") (pinfunction "GPIO15_14") (pintype "unspecified"))
    )
    (net (code "61") (name "Net-(U1-GPIO16)") (class "Default")
      (node (ref "R10") (pin "1") (pinfunction "1_1") (pintype "input"))
      (node (ref "U1") (pin "16") (pinfunction "GPIO16_16") (pintype "unspecified"))
    )
    (net (code "62") (name "Net-(U1-GPIO17)") (class "Default")
      (node (ref "R16") (pin "1") (pinfunction "1_1") (pintype "input"))
      (node (ref "U1") (pin "17") (pinfunction "GPIO17_17") (pintype "unspecified"))
    )
    (net (code "63") (name "Net-(U1-GPIO18)") (class "Default")
      (node (ref "R11") (pin "1") (pinfunction "1_1") (pintype "input"))
      (node (ref "U1") (pin "18") (pinfunction "GPIO18_18") (pintype "unspecified"))
    )
    (net (code "64") (name "Net-(U1-GPIO19)") (class "Default")
      (node (ref "R21") (pin "1") (pinfunction "1_1") (pintype "input"))
      (node (ref "U1") (pin "19") (pinfunction "GPIO19_19") (pintype "unspecified"))
    )
    (net (code "65") (name "Net-(U1-GPIO40_ADC0)") (class "Default")
      (node (ref "R24") (pin "1") (pinfunction "1_1") (pintype "input"))
      (node (ref "U1") (pin "49") (pinfunction "GPIO40_ADC0_49") (pintype "unspecified"))
    )
    (net (code "66") (name "Net-(U1-GPIO41_ADC1)") (class "Default")
      (node (ref "R22") (pin "1") (pinfunction "1_1") (pintype "input"))
      (node (ref "U1") (pin "52") (pinfunction "GPIO41_ADC1_52") (pintype "unspecified"))
    )
    (net (code "67") (name "Net-(U1-GPIO42_ADC2)") (class "Default")
      (node (ref "R17") (pin "1") (pinfunction "1_1") (pintype "input"))
      (node (ref "U1") (pin "53") (pinfunction "GPIO42_ADC2_53") (pintype "unspecified"))
    )
    (net (code "68") (name "Net-(U1-GPIO43_ADC3)") (class "Default")
      (node (ref "R18") (pin "1") (pinfunction "1_1") (pintype "input"))
      (node (ref "U1") (pin "54") (pinfunction "GPIO43_ADC3_54") (pintype "unspecified"))
    )
    (net (code "69") (name "Net-(U1-GPIO44_ADC4)") (class "Default")
      (node (ref "R14") (pin "1") (pinfunction "1_1") (pintype "input"))
      (node (ref "U1") (pin "55") (pinfunction "GPIO44_ADC4_55") (pintype "unspecified"))
    )
    (net (code "70") (name "Net-(U1-GPIO45_ADC5)") (class "Default")
      (node (ref "R15") (pin "1") (pinfunction "1_1") (pintype "input"))
      (node (ref "U1") (pin "56") (pinfunction "GPIO45_ADC5_56") (pintype "unspecified"))
    )
    (net (code "71") (name "Net-(U1-GPIO46_ADC6)") (class "Default")
      (node (ref "R12") (pin "1") (pinfunction "1_1") (pintype "input"))
      (node (ref "U1") (pin "57") (pinfunction "GPIO46_ADC6_57") (pintype "unspecified"))
    )
    (net (code "72") (name "Net-(U1-GPIO47_ADC7)") (class "Default")
      (node (ref "R13") (pin "1") (pinfunction "1_1") (pintype "input"))
      (node (ref "U1") (pin "58") (pinfunction "GPIO47_ADC7_58") (pintype "unspecified"))
    )
    (net (code "73") (name "Net-(U1-QSPI_SCLK)") (class "Default")
      (node (ref "U1") (pin "71") (pinfunction "QSPI_SCLK_71") (pintype "unspecified"))
      (node (ref "U2") (pin "6") (pinfunction "CLK_6") (pintype "unspecified"))
    )
    (net (code "74") (name "Net-(U1-QSPI_SD0)") (class "Default")
      (node (ref "U1") (pin "72") (pinfunction "QSPI_SD0_72") (pintype "unspecified"))
      (node (ref "U2") (pin "5") (pinfunction "DI_5") (pintype "unspecified"))
    )
    (net (code "75") (name "Net-(U1-QSPI_SD1)") (class "Default")
      (node (ref "U1") (pin "74") (pinfunction "QSPI_SD1_74") (pintype "unspecified"))
      (node (ref "U2") (pin "2") (pinfunction "DO_2") (pintype "unspecified"))
    )
    (net (code "76") (name "Net-(U1-QSPI_SD2)") (class "Default")
      (node (ref "U1") (pin "73") (pinfunction "QSPI_SD2_73") (pintype "unspecified"))
      (node (ref "U2") (pin "3") (pinfunction "IO2_3") (pintype "unspecified"))
    )
    (net (code "77") (name "Net-(U1-QSPI_SD3)") (class "Default")
      (node (ref "U1") (pin "70") (pinfunction "QSPI_SD3_70") (pintype "unspecified"))
      (node (ref "U2") (pin "7") (pinfunction "IO3_7") (pintype "unspecified"))
    )
    (net (code "78") (name "Net-(U1-QSPI_SS)") (class "Default")
      (node (ref "R2") (pin "1") (pinfunction "1_1") (pintype "input"))
      (node (ref "U1") (pin "75") (pinfunction "QSPI_SS_75") (pintype "unspecified"))
      (node (ref "U2") (pin "1") (pinfunction "CS#_1") (pintype "unspecified"))
    )
    (net (code "79") (name "Net-(U1-XIN)") (class "Default")
      (node (ref "C3") (pin "1") (pinfunction "1_1") (pintype "input"))
      (node (ref "U1") (pin "30") (pinfunction "XIN_30") (pintype "unspecified"))
      (node (ref "X2") (pin "1") (pinfunction "OSC1_1") (pintype "unspecified"))
    )
    (net (code "80") (name "Net-(U1-XOUT)") (class "Default")
      (node (ref "R23") (pin "1") (pinfunction "1_1") (pintype "input"))
      (node (ref "U1") (pin "31") (pinfunction "XOUT_31") (pintype "unspecified"))
    )
    (net (code "81") (name "Net-(X2-OSC2)") (class "Default")
      (node (ref "C4") (pin "1") (pinfunction "1_1") (pintype "input"))
      (node (ref "R23") (pin "2") (pinfunction "2_2") (pintype "input"))
      (node (ref "X2") (pin "3") (pinfunction "OSC2_3") (pintype "unspecified"))
    )
    (net (code "82") (name "VCC") (class "Default")
      (node (ref "C17") (pin "2") (pinfunction "2_2") (pintype "unspecified"))
      (node (ref "C18") (pin "2") (pinfunction "2_2") (pintype "unspecified"))
      (node (ref "U3") (pin "3") (pinfunction "VIN_3") (pintype "unspecified"))
      (node (ref "U4") (pin "3") (pinfunction "In_3") (pintype "unspecified"))
      (node (ref "U5") (pin "19") (pinfunction "VCC1_19") (pintype "unspecified"))
      (node (ref "U6") (pin "19") (pinfunction "VCC1_19") (pintype "unspecified"))
    )
    (net (code "83") (name "VCC18") (class "Default")
      (node (ref "C10") (pin "1") (pinfunction "1_1") (pintype "unspecified"))
      (node (ref "C13") (pin "1") (pinfunction "1_1") (pintype "unspecified"))
      (node (ref "C19") (pin "2") (pinfunction "2_2") (pintype "unspecified"))
      (node (ref "C5") (pin "1") (pinfunction "1_1") (pintype "unspecified"))
      (node (ref "C7") (pin "1") (pinfunction "1_1") (pintype "unspecified"))
      (node (ref "U1") (pin "10") (pinfunction "DVDD_10") (pintype "unspecified"))
      (node (ref "U1") (pin "32") (pinfunction "DVDD_32") (pintype "unspecified"))
      (node (ref "U1") (pin "51") (pinfunction "DVDD_51") (pintype "unspecified"))
      (node (ref "U4") (pin "2") (pinfunction "Out_2") (pintype "unspecified"))
      (node (ref "U4") (pin "4") (pinfunction "TAB_4") (pintype "unspecified"))
    )
    (net (code "84") (name "VCC33") (class "Default")
      (node (ref "C1") (pin "2") (pinfunction "2_2") (pintype "unspecified"))
      (node (ref "C11") (pin "2") (pinfunction "2_2") (pintype "unspecified"))
      (node (ref "C12") (pin "1") (pinfunction "1_1") (pintype "unspecified"))
      (node (ref "C14") (pin "2") (pinfunction "2_2") (pintype "unspecified"))
      (node (ref "C15") (pin "1") (pinfunction "1_1") (pintype "unspecified"))
      (node (ref "C16") (pin "2") (pinfunction "2_2") (pintype "unspecified"))
      (node (ref "C2") (pin "2") (pinfunction "2_2") (pintype "unspecified"))
      (node (ref "C6") (pin "1") (pinfunction "1_1") (pintype "unspecified"))
      (node (ref "C8") (pin "2") (pinfunction "2_2") (pintype "unspecified"))
      (node (ref "C9") (pin "1") (pinfunction "1_1") (pintype "unspecified"))
      (node (ref "R1") (pin "2") (pinfunction "2_2") (pintype "input"))
      (node (ref "R9") (pin "2") (pinfunction "2_2") (pintype "input"))
      (node (ref "U1") (pin "15") (pinfunction "IOVDD_15") (pintype "unspecified"))
      (node (ref "U1") (pin "24") (pinfunction "IOVDD_24") (pintype "unspecified"))
      (node (ref "U1") (pin "29") (pinfunction "IOVDD_29") (pintype "unspecified"))
      (node (ref "U1") (pin "35") (pinfunction "RUN_35") (pintype "unspecified"))
      (node (ref "U1") (pin "41") (pinfunction "IOVDD_41") (pintype "unspecified"))
      (node (ref "U1") (pin "5") (pinfunction "IOVDD_5") (pintype "unspecified"))
      (node (ref "U1") (pin "50") (pinfunction "IOVDD_50") (pintype "unspecified"))
      (node (ref "U1") (pin "59") (pinfunction "ADC_AVDD_59") (pintype "unspecified"))
      (node (ref "U1") (pin "60") (pinfunction "IOVDD_60") (pintype "unspecified"))
      (node (ref "U1") (pin "61") (pinfunction "VREG_AVDD_61") (pintype "unspecified"))
      (node (ref "U1") (pin "64") (pinfunction "VREG_VIN_64") (pintype "unspecified"))
      (node (ref "U1") (pin "68") (pinfunction "USB_OTP_VDD_68") (pintype "unspecified"))
      (node (ref "U1") (pin "69") (pinfunction "QSPI_IOVDD_69") (pintype "unspecified"))
      (node (ref "U1") (pin "76") (pinfunction "IOVDD_76") (pintype "unspecified"))
      (node (ref "U2") (pin "8") (pinfunction "VCC_8") (pintype "unspecified"))
      (node (ref "U3") (pin "2") (pinfunction "VOUT_2") (pintype "unspecified"))
      (node (ref "U3") (pin "4") (pinfunction "VOUT_4") (pintype "unspecified"))
    )
    (net (code "85") (name "unconnected-(U1-VREG_FB-Pad65)") (class "Default")
      (node (ref "U1") (pin "65") (pinfunction "VREG_FB_65") (pintype "unspecified"))
    )
    (net (code "86") (name "unconnected-(U1-VREG_LX-Pad63)") (class "Default")
      (node (ref "U1") (pin "63") (pinfunction "VREG_LX_63") (pintype "unspecified"))
    )
    (net (code "87") (name "unconnected-(USB1-CC1-Pad4)") (class "Default")
      (node (ref "USB1") (pin "4") (pinfunction "CC1_4") (pintype "unspecified"))
    )
    (net (code "88") (name "unconnected-(USB1-CC2-Pad10)") (class "Default")
      (node (ref "USB1") (pin "10") (pinfunction "CC2_10") (pintype "unspecified"))
    )
    (net (code "89") (name "unconnected-(USB1-SBU1-Pad9)") (class "Default")
      (node (ref "USB1") (pin "9") (pinfunction "SBU1_9") (pintype "unspecified+no_connect"))
    )
    (net (code "90") (name "unconnected-(USB1-SBU2-Pad3)") (class "Default")
      (node (ref "USB1") (pin "3") (pinfunction "SBU2_3") (pintype "unspecified+no_connect"))
    )
    (net (code "91") (name "unconnected-(USB1-VBUS-Pad2)") (class "Default")
      (node (ref "USB1") (pin "2") (pinfunction "VBUS_2") (pintype "unspecified"))
    )
    (net (code "92") (name "unconnected-(USB1-VBUS-Pad11)") (class "Default")
      (node (ref "USB1") (pin "11") (pinfunction "VBUS_11") (pintype "unspecified"))
    )
    (net (code "93") (name "unconnected-(X1-Pad5)") (class "Default")
      (node (ref "X1") (pin "5") (pinfunction "5_5") (pintype "input"))
    )
    (net (code "94") (name "unconnected-(X1-Pad6)") (class "Default")
      (node (ref "X1") (pin "6") (pinfunction "6_6") (pintype "input"))
    )
    (net (code "95") (name "unconnected-(X1-Pad11)") (class "Default")
      (node (ref "X1") (pin "11") (pinfunction "11_11") (pintype "input"))
    )
    (net (code "96") (name "unconnected-(X1-Pad12)") (class "Default")
      (node (ref "X1") (pin "12") (pinfunction "12_12") (pintype "input"))
    )
    (net (code "97") (name "unconnected-(X1-Pad13)") (class "Default")
      (node (ref "X1") (pin "13") (pinfunction "13_13") (pintype "input"))
    )
    (net (code "98") (name "unconnected-(X1-Pad14)") (class "Default")
      (node (ref "X1") (pin "14") (pinfunction "14_14") (pintype "input"))
    )
    (net (code "99") (name "unconnected-(X1-Pad15)") (class "Default")
      (node (ref "X1") (pin "15") (pinfunction "15_15") (pintype "input"))
    )
    (net (code "100") (name "unconnected-(X2-GND-Pad2)") (class "Default")
      (node (ref "X2") (pin "2") (pinfunction "GND_2") (pintype "unspecified"))
    )
    (net (code "101") (name "unconnected-(X2-GND-Pad4)") (class "Default")
      (node (ref "X2") (pin "4") (pinfunction "GND_4") (pintype "unspecified"))
    )
  )
)
